# LOOM_-_HV_BOX.net
KiCad netlist of a schematic drawn in Altium Designer
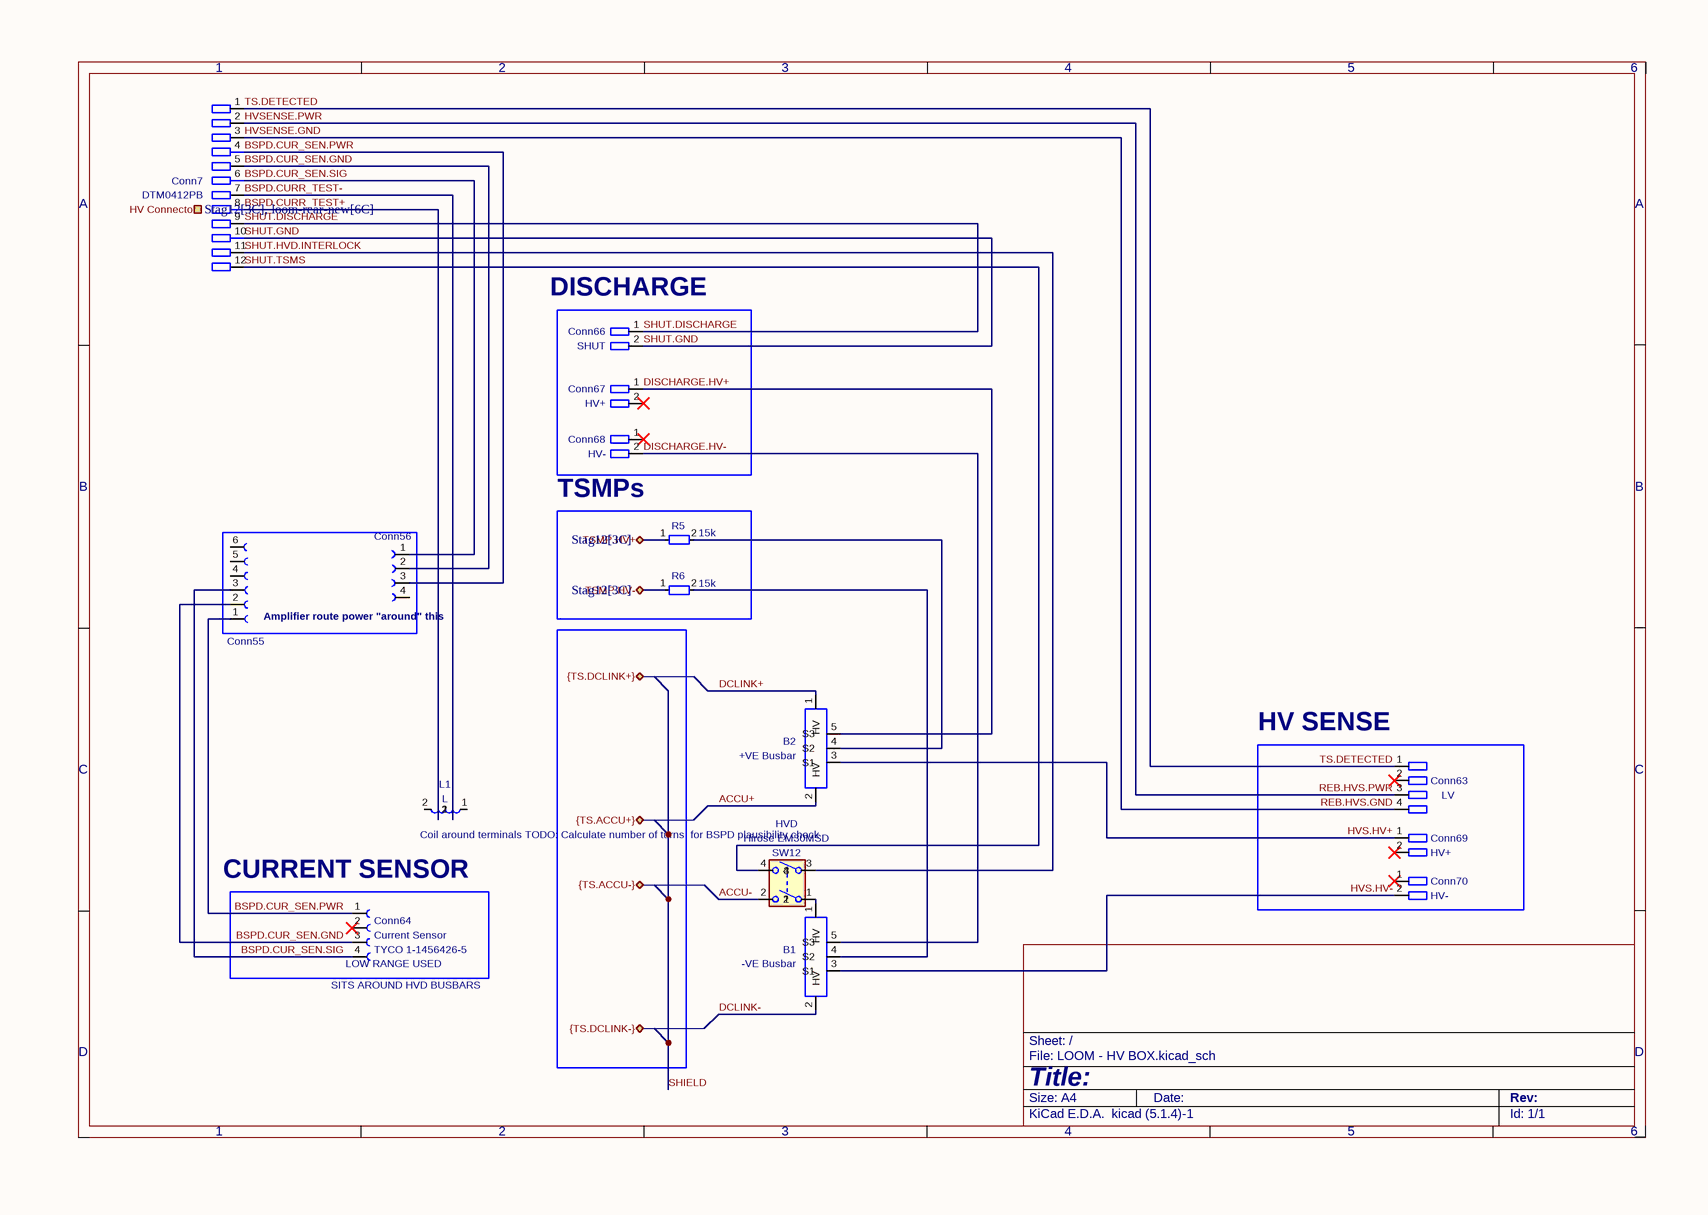
[diagram p0: LOOM - HV BOX.SchDoc]

(export (version "E")
  (design (tool "Eeschema 10.0.6"))
  (components
    (comp (ref "B1") (value "-VE Busbar") (libsource (lib "Connectors_SUFST") (part "Bus_Bar")))
    (comp (ref "B2") (value "+VE Busbar") (libsource (lib "Connectors_SUFST") (part "Bus_Bar")))
    (comp (ref "Conn7")
      (value "Deutsch_DTM_12P_Pin")
      (fields (field (name "P/N") "DTM0412PB"))
      (libsource (lib "Connectors_SUFST") (part "Deutsch_DTM_12P_Pin"))
    )
    (comp (ref "Conn55")
      (value "Molex_3x2S_Recepticle")
      (libsource (lib "Connectors_SUFST") (part "Molex_3x2S_Recepticle"))
    )
    (comp (ref "Conn56")
      (value "Molex_2x2S_Recepticle")
      (libsource (lib "Connectors_SUFST") (part "Molex_2x2S_Recepticle"))
    )
    (comp (ref "Conn63")
      (value "~")
      (fields (field (name "NAME") "LV"))
      (libsource (lib "*") (part "Molex_2x2P_Horizontal_1"))
    )
    (comp (ref "Conn64")
      (value "Current Sensor")
      (fields (field (name "P/N") "TYCO 1-1456426-5"))
      (libsource (lib "Connectors_SUFST") (part "Current Sensor Connector"))
    )
    (comp (ref "Conn66")
      (value "Molex_2x1P_Horizontal_THT")
      (fields (field (name "NAME") "SHUT"))
      (libsource (lib "Connectors_SUFST") (part "Molex_2x1P_Horizontal_THT"))
    )
    (comp (ref "Conn67")
      (value "Molex_2x1P_Horizontal_THT")
      (fields (field (name "NAME") "HV+"))
      (libsource (lib "Connectors_SUFST") (part "Molex_2x1P_Horizontal_THT"))
    )
    (comp (ref "Conn68")
      (value "Molex_2x1P_Horizontal_THT")
      (fields (field (name "NAME") "HV-"))
      (libsource (lib "Connectors_SUFST") (part "Molex_2x1P_Horizontal_THT"))
    )
    (comp (ref "Conn69")
      (value "Molex_2x1P_Horizontal_THT")
      (fields (field (name "NAME") "HV+"))
      (libsource (lib "") (part "Molex_2x1P_Horizontal_THT_1"))
    )
    (comp (ref "Conn70")
      (value "Molex_2x1P_Horizontal_THT")
      (fields (field (name "NAME") "HV-"))
      (libsource (lib "") (part "Molex_2x1P_Horizontal_THT_1"))
    )
    (comp (ref "L1") (value "L") (libsource (lib "Device") (part "L")))
    (comp (ref "R5") (value "15k") (libsource (lib "Device") (part "R_Small")))
    (comp (ref "R6") (value "15k") (libsource (lib "Device") (part "R_Small")))
    (comp (ref "SW12")
      (value "Hirose EM30MSD")
      (fields (field (name "CONN NAME") "HVD"))
      (libsource (lib "Switch") (part "SW_DPST"))
    )
  )
  (nets
    (net (code "5") (name "/ACCU+") (class "Default")
      (node (ref "B2") (pin "2") (pinfunction "HV_2") (pintype "passive"))
    )
    (net (code "6") (name "/ACCU-") (class "Default")
      (node (ref "SW12") (pin "2") (pinfunction "2_2") (pintype "passive"))
    )
    (net (code "7") (name "/BSPD.CURR_TEST+") (class "Default")
      (node (ref "Conn7") (pin "8") (pinfunction "8_8") (pintype "passive"))
    )
    (net (code "8") (name "/BSPD.CURR_TEST-") (class "Default")
      (node (ref "Conn7") (pin "7") (pinfunction "7_7") (pintype "passive"))
    )
    (net (code "9") (name "/BSPD.CUR_SEN.GND") (class "Default")
      (node (ref "Conn55") (pin "2") (pinfunction "2_2") (pintype "passive"))
      (node (ref "Conn56") (pin "2") (pinfunction "2_2") (pintype "passive"))
      (node (ref "Conn64") (pin "3") (pinfunction "3_3") (pintype "passive"))
      (node (ref "Conn7") (pin "5") (pinfunction "5_5") (pintype "passive"))
    )
    (net (code "10") (name "/BSPD.CUR_SEN.PWR") (class "Default")
      (node (ref "Conn55") (pin "1") (pinfunction "1_1") (pintype "passive"))
      (node (ref "Conn56") (pin "3") (pinfunction "3_3") (pintype "passive"))
      (node (ref "Conn64") (pin "1") (pinfunction "1_1") (pintype "passive"))
      (node (ref "Conn7") (pin "4") (pinfunction "4_4") (pintype "passive"))
    )
    (net (code "11") (name "/BSPD.CUR_SEN.SIG") (class "Default")
      (node (ref "Conn55") (pin "3") (pinfunction "3_3") (pintype "passive"))
      (node (ref "Conn56") (pin "1") (pinfunction "1_1") (pintype "passive"))
      (node (ref "Conn64") (pin "4") (pinfunction "4_4") (pintype "passive"))
      (node (ref "Conn7") (pin "6") (pinfunction "6_6") (pintype "passive"))
    )
    (net (code "12") (name "/DCLINK+") (class "Default")
      (node (ref "B2") (pin "1") (pinfunction "HV_1") (pintype "passive"))
    )
    (net (code "13") (name "/DCLINK-") (class "Default")
      (node (ref "B1") (pin "2") (pinfunction "HV_2") (pintype "passive"))
    )
    (net (code "14") (name "/DISCHARGE.HV+") (class "Default")
      (node (ref "B2") (pin "5") (pinfunction "S3_5") (pintype "passive"))
      (node (ref "Conn67") (pin "1") (pinfunction "1_1") (pintype "passive"))
    )
    (net (code "15") (name "/DISCHARGE.HV-") (class "Default")
      (node (ref "B1") (pin "5") (pinfunction "S3_5") (pintype "passive"))
      (node (ref "Conn68") (pin "2") (pinfunction "2_2") (pintype "passive"))
    )
    (net (code "17") (name "/HVS.HV+") (class "Default")
      (node (ref "B2") (pin "3") (pinfunction "S1_3") (pintype "passive"))
      (node (ref "Conn69") (pin "1") (pinfunction "1_1") (pintype "passive"))
    )
    (net (code "18") (name "/HVS.HV-") (class "Default")
      (node (ref "B1") (pin "3") (pinfunction "S1_3") (pintype "passive"))
      (node (ref "Conn70") (pin "2") (pinfunction "2_2") (pintype "passive"))
    )
    (net (code "19") (name "/HVSENSE.GND") (class "Default")
      (node (ref "Conn63") (pin "4") (pinfunction "4_4") (pintype "passive"))
      (node (ref "Conn7") (pin "3") (pinfunction "3_3") (pintype "passive"))
    )
    (net (code "20") (name "/HVSENSE.PWR") (class "Default")
      (node (ref "Conn63") (pin "3") (pinfunction "3_3") (pintype "passive"))
      (node (ref "Conn7") (pin "2") (pinfunction "2_2") (pintype "passive"))
    )
    (net (code "22") (name "/SHUT.DISCHARGE") (class "Default")
      (node (ref "Conn66") (pin "1") (pinfunction "1_1") (pintype "passive"))
      (node (ref "Conn7") (pin "9") (pinfunction "9_9") (pintype "passive"))
    )
    (net (code "23") (name "/SHUT.GND") (class "Default")
      (node (ref "Conn66") (pin "2") (pinfunction "2_2") (pintype "passive"))
      (node (ref "Conn7") (pin "10") (pinfunction "10_10") (pintype "passive"))
    )
    (net (code "24") (name "/SHUT.HVD.INTERLOCK") (class "Default")
      (node (ref "Conn7") (pin "11") (pinfunction "11_11") (pintype "passive"))
      (node (ref "SW12") (pin "3") (pinfunction "3_3") (pintype "passive"))
    )
    (net (code "25") (name "/SHUT.TSMS") (class "Default")
      (node (ref "Conn7") (pin "12") (pinfunction "12_12") (pintype "passive"))
      (node (ref "SW12") (pin "4") (pinfunction "4_4") (pintype "passive"))
    )
    (net (code "26") (name "/TS.DETECTED") (class "Default")
      (node (ref "Conn63") (pin "1") (pinfunction "1_1") (pintype "passive"))
      (node (ref "Conn7") (pin "1") (pinfunction "1_1") (pintype "passive"))
    )
    (net (code "27") (name "/TSMP.HV+") (class "Default")
      (node (ref "R5") (pin "1") (pinfunction "1_1") (pintype "passive"))
    )
    (net (code "28") (name "/TSMP.HV-") (class "Default")
      (node (ref "R6") (pin "1") (pinfunction "1_1") (pintype "passive"))
    )
    (net (code "33") (name "Net-(B1-HV-Pad1)") (class "Default")
      (node (ref "B1") (pin "1") (pinfunction "HV_1") (pintype "passive"))
      (node (ref "SW12") (pin "1") (pinfunction "1_1") (pintype "passive"))
    )
    (net (code "34") (name "Net-(B1-S2)") (class "Default")
      (node (ref "B1") (pin "4") (pinfunction "S2_4") (pintype "passive"))
      (node (ref "R6") (pin "2") (pinfunction "2_2") (pintype "passive"))
    )
    (net (code "35") (name "Net-(B2-S2)") (class "Default")
      (node (ref "B2") (pin "4") (pinfunction "S2_4") (pintype "passive"))
      (node (ref "R5") (pin "2") (pinfunction "2_2") (pintype "passive"))
    )
    (net (code "36") (name "unconnected-(Conn55-Pad4)") (class "Default")
      (node (ref "Conn55") (pin "4") (pinfunction "4_4") (pintype "passive"))
    )
    (net (code "37") (name "unconnected-(Conn55-Pad5)") (class "Default")
      (node (ref "Conn55") (pin "5") (pinfunction "5_5") (pintype "passive"))
    )
    (net (code "38") (name "unconnected-(Conn55-Pad6)") (class "Default")
      (node (ref "Conn55") (pin "6") (pinfunction "6_6") (pintype "passive"))
    )
    (net (code "39") (name "unconnected-(Conn56-Pad4)") (class "Default")
      (node (ref "Conn56") (pin "4") (pinfunction "4_4") (pintype "passive"))
    )
    (net (code "40") (name "unconnected-(Conn63-Pad2)") (class "Default")
      (node (ref "Conn63") (pin "2") (pinfunction "2_2") (pintype "passive+no_connect"))
    )
    (net (code "41") (name "unconnected-(Conn64-Pad2)") (class "Default")
      (node (ref "Conn64") (pin "2") (pinfunction "2_2") (pintype "passive+no_connect"))
    )
    (net (code "42") (name "unconnected-(Conn67-Pad2)") (class "Default")
      (node (ref "Conn67") (pin "2") (pinfunction "2_2") (pintype "passive+no_connect"))
    )
    (net (code "43") (name "unconnected-(Conn68-Pad1)") (class "Default")
      (node (ref "Conn68") (pin "1") (pinfunction "1_1") (pintype "passive+no_connect"))
    )
    (net (code "44") (name "unconnected-(Conn69-Pad2)") (class "Default")
      (node (ref "Conn69") (pin "2") (pinfunction "2_2") (pintype "passive+no_connect"))
    )
    (net (code "45") (name "unconnected-(Conn70-Pad1)") (class "Default")
      (node (ref "Conn70") (pin "1") (pinfunction "1_1") (pintype "passive+no_connect"))
    )
    (net (code "46") (name "unconnected-(L1-Pad1)") (class "Default")
      (node (ref "L1") (pin "1") (pinfunction "1_1") (pintype "passive"))
    )
    (net (code "47") (name "unconnected-(L1-Pad2)") (class "Default")
      (node (ref "L1") (pin "2") (pinfunction "2_2") (pintype "passive"))
    )
  )
)
